# SCH_Hacker-Card_2025-04-09.net
KiCad netlist of a schematic drawn in EasyEDA
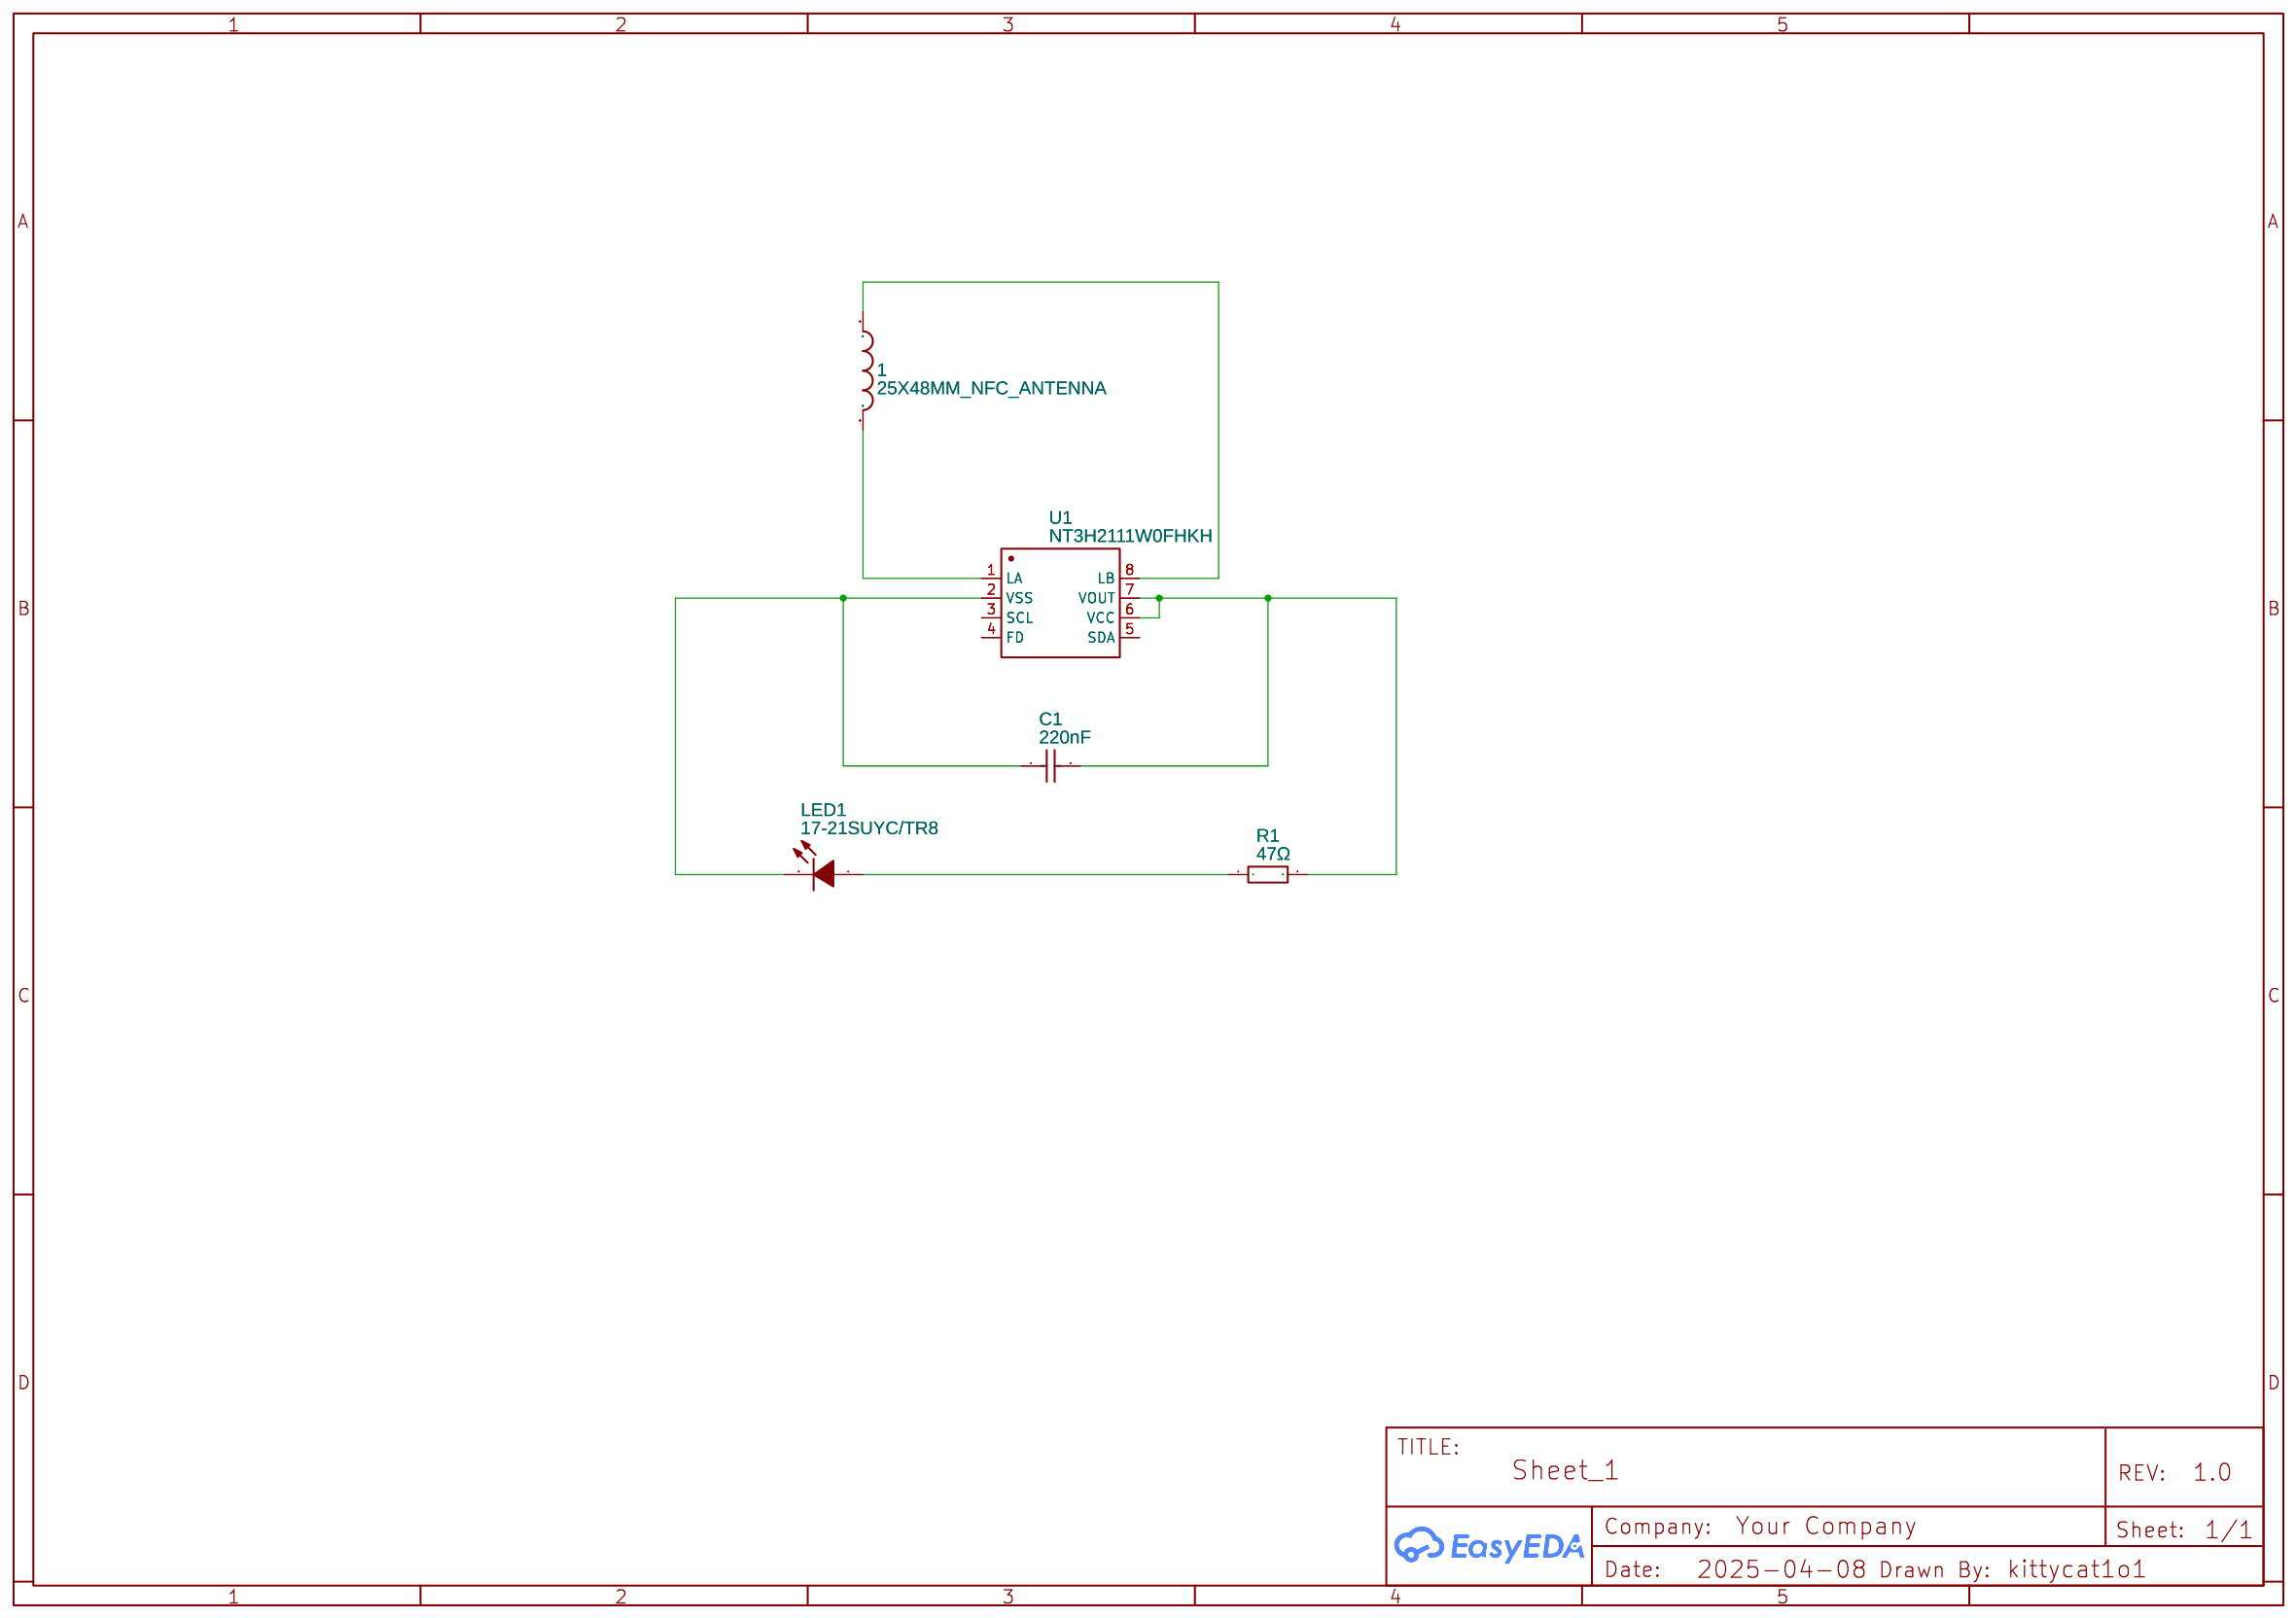
[diagram p0: schematic sheet]

(export (version "E")
  (design (tool "Eeschema 10.0.6"))
  (components
    (comp (ref "1") (value "25X48MM_NFC_ANTENNA") (libsource (lib "") (part "25X48MM_NFC_ANTENNA")))
    (comp (ref "C1")
      (value "220nF")
      (fields
        (field (name "Manufacturer Part") "CL10B224KA8NNNC")
        (field (name "Manufacturer") "SAMSUNG(三星)")
      )
      (libsource (lib "") (part "CL10B224KA8NNNC"))
    )
    (comp (ref "LED1")
      (value "17-21SUYC/TR8")
      (fields (field (name "Manufacturer Part") "KT-0805黄灯") (field (name "Manufacturer") "KENTO"))
      (libsource (lib "") (part "17-21SUYC/TR8"))
    )
    (comp (ref "R1")
      (value "47Ω")
      (fields
        (field (name "Manufacturer Part") "0603WAF470JT5E")
        (field (name "Manufacturer") "UNI-ROYAL(厚声)")
      )
      (libsource (lib "") (part "0603WAF470JT5E"))
    )
    (comp (ref "U1")
      (value "NT3H2111W0FHKH")
      (fields (field (name "Manufacturer") "NXP(恩智浦)"))
      (libsource (lib "") (part "NT3H2111W0FHKH"))
    )
  )
  (nets
    (net (code "1") (name "Net-(LED1-+)") (class "Default")
      (node (ref "LED1") (pin "1") (pinfunction "+_1") (pintype "unspecified"))
      (node (ref "R1") (pin "1") (pinfunction "1_1") (pintype "input"))
    )
    (net (code "2") (name "Net-(LED1--)") (class "Default")
      (node (ref "C1") (pin "1") (pinfunction "1_1") (pintype "input"))
      (node (ref "LED1") (pin "2") (pinfunction "-_2") (pintype "unspecified"))
      (node (ref "U1") (pin "2") (pinfunction "VSS_2") (pintype "unspecified"))
    )
    (net (code "3") (name "Net-(U1-LA)") (class "Default")
      (node (ref "1") (pin "P$2") (pinfunction "P$2_P$2") (pintype "bidirectional"))
      (node (ref "U1") (pin "1") (pinfunction "LA_1") (pintype "unspecified"))
    )
    (net (code "4") (name "Net-(U1-LB)") (class "Default")
      (node (ref "1") (pin "P$1") (pinfunction "P$1_P$1") (pintype "bidirectional"))
      (node (ref "U1") (pin "8") (pinfunction "LB_8") (pintype "unspecified"))
    )
    (net (code "5") (name "Net-(U1-VCC)") (class "Default")
      (node (ref "C1") (pin "2") (pinfunction "2_2") (pintype "input"))
      (node (ref "R1") (pin "2") (pinfunction "2_2") (pintype "input"))
      (node (ref "U1") (pin "6") (pinfunction "VCC_6") (pintype "unspecified"))
      (node (ref "U1") (pin "7") (pinfunction "VOUT_7") (pintype "unspecified"))
    )
    (net (code "6") (name "unconnected-(U1-FD-Pad4)") (class "Default")
      (node (ref "U1") (pin "4") (pinfunction "FD_4") (pintype "unspecified"))
    )
    (net (code "7") (name "unconnected-(U1-SCL-Pad3)") (class "Default")
      (node (ref "U1") (pin "3") (pinfunction "SCL_3") (pintype "unspecified"))
    )
    (net (code "8") (name "unconnected-(U1-SDA-Pad5)") (class "Default")
      (node (ref "U1") (pin "5") (pinfunction "SDA_5") (pintype "unspecified"))
    )
  )
)
